# rgb.net
KiCad netlist of a schematic drawn in EAGLE
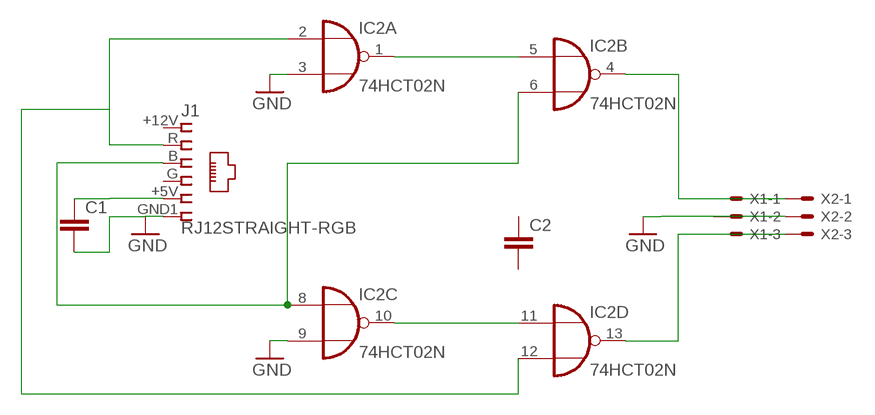
[diagram p0: schematic, sheet 1]

(export (version "E")
  (design (tool "Eeschema 10.0.6"))
  (components
    (comp (ref "C1")
      (value "C-EU025-025X050")
      (footprint "eagle-import:C025-025X050")
      (libsource (lib "eagle-import") (part "C-EU025-025X050"))
    )
    (comp (ref "C2")
      (value "C-EU025-025X050")
      (footprint "eagle-import:C025-025X050")
      (libsource (lib "eagle-import") (part "C-EU025-025X050"))
    )
    (comp (ref "IC2")
      (value "74HCT02N")
      (footprint "eagle-import:DIL14")
      (libsource (lib "eagle-import") (part "7402NHCT"))
    )
    (comp (ref "J1")
      (value "RJ12STRAIGHT-RGB")
      (footprint "eagle-import:RJ12-STRAIGHT-RGB")
      (libsource (lib "eagle-import") (part "RJ12STRAIGHT-RGB"))
    )
    (comp (ref "X1")
      (value "KK-156-3")
      (footprint "eagle-import:KK-156-3")
      (libsource (lib "eagle-import") (part "KK-156-3"))
    )
    (comp (ref "X2")
      (value "KK-156-3")
      (footprint "eagle-import:KK-156-3")
      (fields (field (name "OC_FARNELL") "unknown") (field (name "OC_NEWARK") "unknown"))
      (libsource (lib "eagle-import") (part "KK-156-3"))
    )
  )
  (nets
    (net (code "1") (name "/1") (class "Default")
      (node (ref "J1") (pin "+12V") (pinfunction "1_+12V") (pintype "power_in"))
    )
    (net (code "2") (name "/4") (class "Default")
      (node (ref "J1") (pin "G") (pinfunction "4_G") (pintype "power_in"))
    )
    (net (code "3") (name "GND") (class "Default")
      (node (ref "C1") (pin "2") (pinfunction "2_2") (pintype "passive"))
      (node (ref "IC2") (pin "3") (pinfunction "I1_3") (pintype "input"))
      (node (ref "IC2") (pin "9") (pinfunction "I1_9") (pintype "input"))
      (node (ref "J1") (pin "GND1") (pinfunction "6_GND1") (pintype "power_in"))
      (node (ref "X1") (pin "2") (pinfunction "S_2") (pintype "passive"))
      (node (ref "X2") (pin "2") (pinfunction "S_2") (pintype "passive"))
    )
    (net (code "4") (name "Net-(IC2A-I0)") (class "Default")
      (node (ref "IC2") (pin "12") (pinfunction "I1_12") (pintype "input"))
      (node (ref "IC2") (pin "2") (pinfunction "I0_2") (pintype "input"))
      (node (ref "J1") (pin "R") (pinfunction "2_R") (pintype "bidirectional"))
    )
    (net (code "5") (name "Net-(IC2A-O)") (class "Default")
      (node (ref "IC2") (pin "1") (pinfunction "O_1") (pintype "output"))
      (node (ref "IC2") (pin "5") (pinfunction "I0_5") (pintype "input"))
    )
    (net (code "6") (name "Net-(IC2B-I1)") (class "Default")
      (node (ref "IC2") (pin "6") (pinfunction "I1_6") (pintype "input"))
      (node (ref "IC2") (pin "8") (pinfunction "I0_8") (pintype "input"))
      (node (ref "J1") (pin "B") (pinfunction "3_B") (pintype "bidirectional"))
    )
    (net (code "7") (name "Net-(IC2B-O)") (class "Default")
      (node (ref "IC2") (pin "4") (pinfunction "O_4") (pintype "output"))
      (node (ref "X1") (pin "1") (pinfunction "S_1") (pintype "passive"))
      (node (ref "X2") (pin "1") (pinfunction "S_1") (pintype "passive"))
    )
    (net (code "8") (name "Net-(IC2C-O)") (class "Default")
      (node (ref "IC2") (pin "10") (pinfunction "O_10") (pintype "output"))
      (node (ref "IC2") (pin "11") (pinfunction "I0_11") (pintype "input"))
    )
    (net (code "9") (name "Net-(IC2D-O)") (class "Default")
      (node (ref "IC2") (pin "13") (pinfunction "O_13") (pintype "output"))
      (node (ref "X1") (pin "3") (pinfunction "S_3") (pintype "passive"))
      (node (ref "X2") (pin "3") (pinfunction "S_3") (pintype "passive"))
    )
    (net (code "10") (name "Net-(J1-5)") (class "Default")
      (node (ref "C1") (pin "1") (pinfunction "1_1") (pintype "passive"))
      (node (ref "J1") (pin "+5V") (pinfunction "5_+5V") (pintype "power_in"))
    )
    (net (code "11") (name "unconnected-(C2-Pad1)") (class "Default")
      (node (ref "C2") (pin "1") (pinfunction "1_1") (pintype "passive"))
    )
    (net (code "12") (name "unconnected-(C2-Pad2)") (class "Default")
      (node (ref "C2") (pin "2") (pinfunction "2_2") (pintype "passive"))
    )
  )
)
